# AS3364_DG412_bus_mixer_v1_3.net
KiCad netlist of a schematic drawn in EAGLE
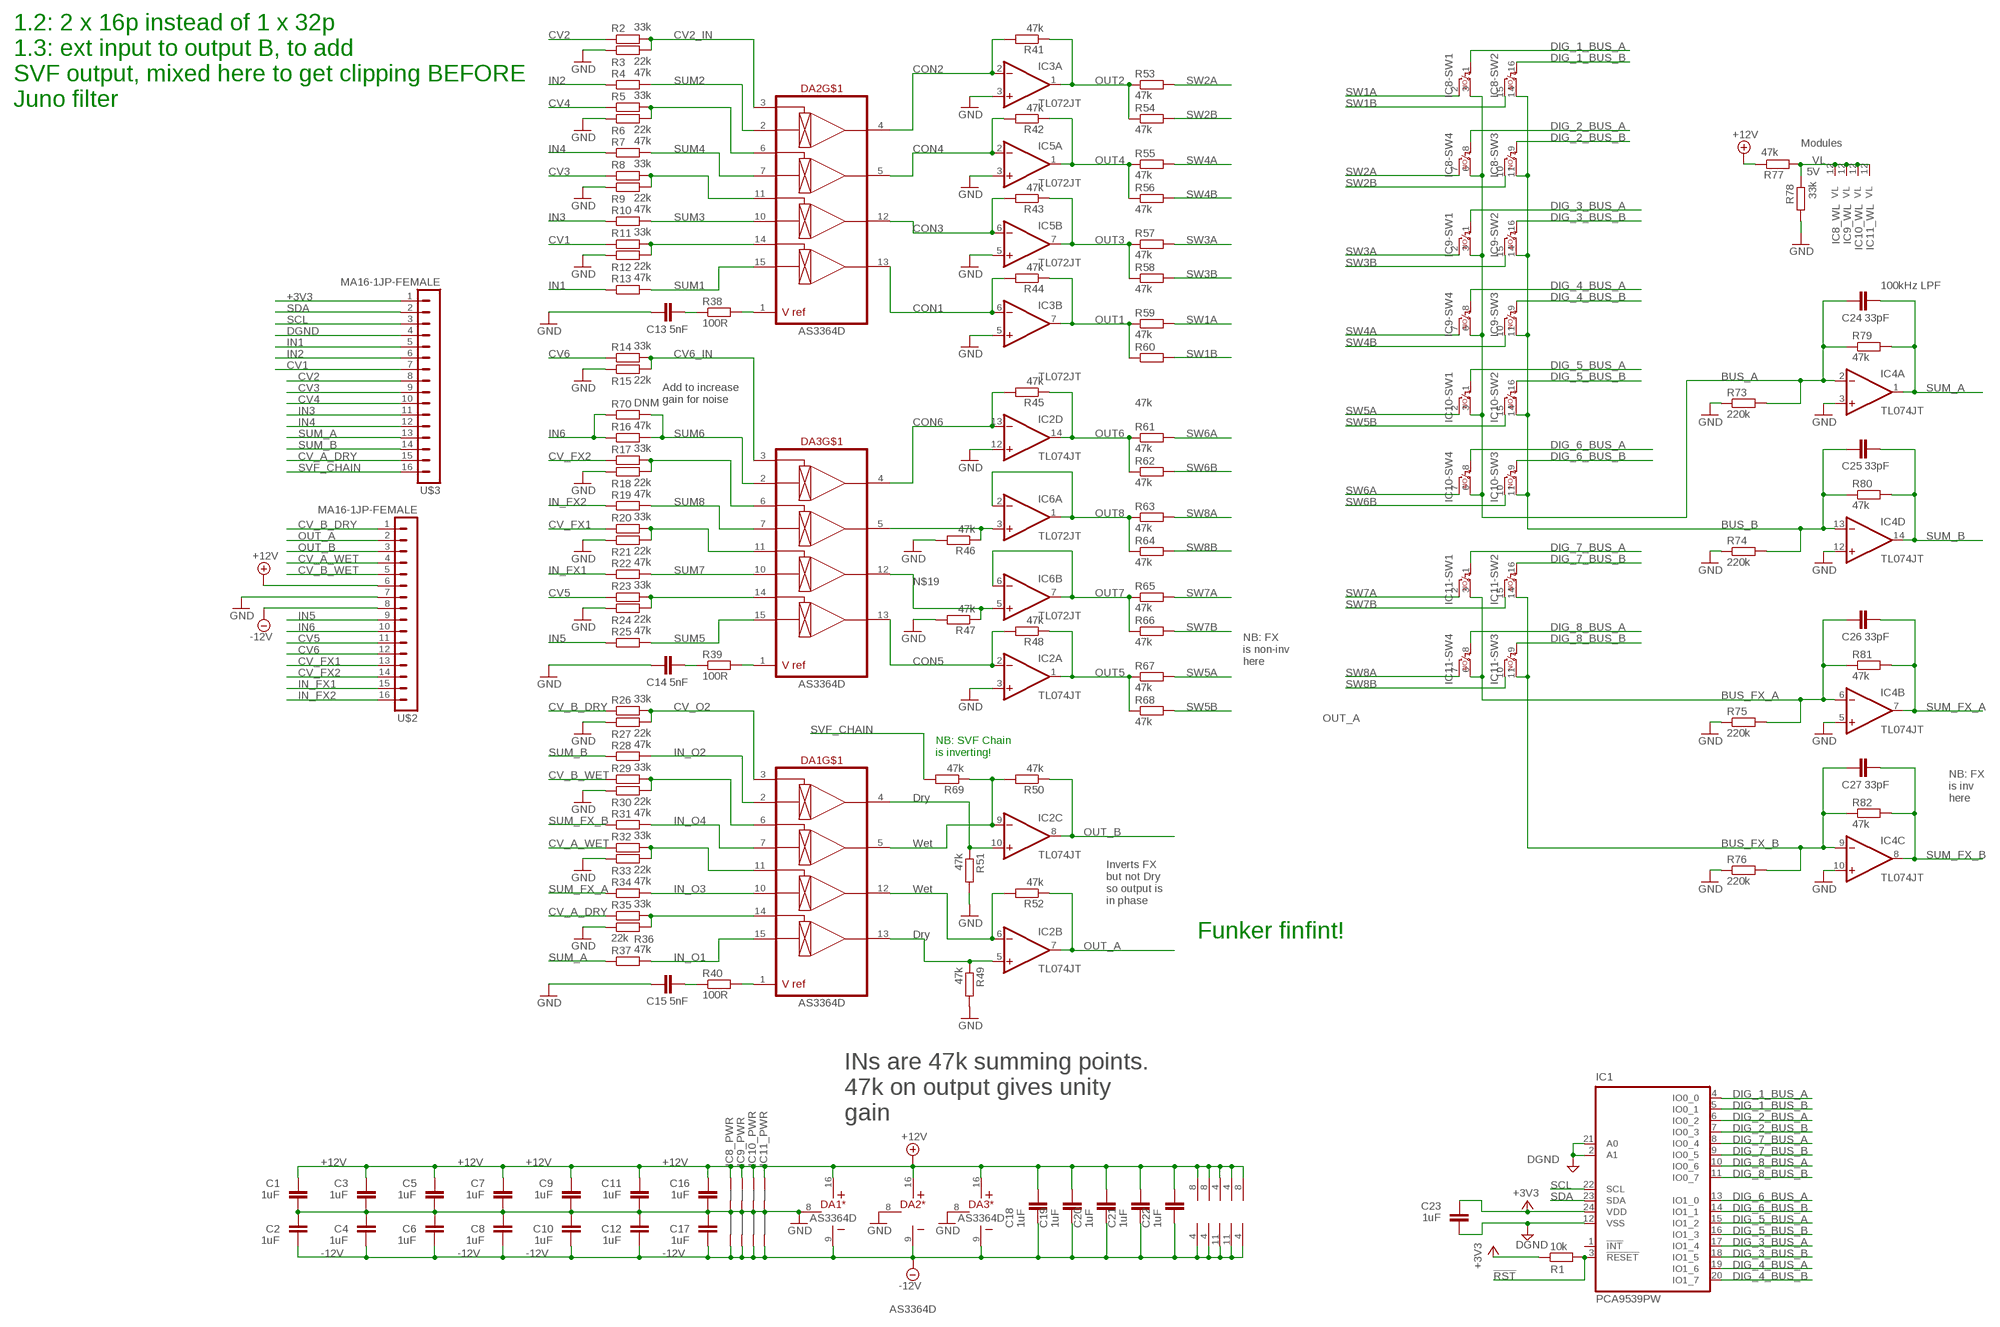
[diagram p0: schematic, sheet 1]

(export (version "E")
  (design (tool "Eeschema 10.0.6"))
  (components
    (comp (ref "C1")
      (value "1uF")
      (footprint "eagle-import:C0402-J")
      (libsource (lib "eagle-import") (part "C-EU-J0402"))
    )
    (comp (ref "C2")
      (value "1uF")
      (footprint "eagle-import:C0402-J")
      (libsource (lib "eagle-import") (part "C-EU-J0402"))
    )
    (comp (ref "C3")
      (value "1uF")
      (footprint "eagle-import:C0402-J")
      (libsource (lib "eagle-import") (part "C-EU-J0402"))
    )
    (comp (ref "C4")
      (value "1uF")
      (footprint "eagle-import:C0402-J")
      (libsource (lib "eagle-import") (part "C-EU-J0402"))
    )
    (comp (ref "C5")
      (value "1uF")
      (footprint "eagle-import:C0402-J")
      (libsource (lib "eagle-import") (part "C-EU-J0402"))
    )
    (comp (ref "C6")
      (value "1uF")
      (footprint "eagle-import:C0402-J")
      (libsource (lib "eagle-import") (part "C-EU-J0402"))
    )
    (comp (ref "C7")
      (value "1uF")
      (footprint "eagle-import:C0402-J")
      (libsource (lib "eagle-import") (part "C-EU-J0402"))
    )
    (comp (ref "C8")
      (value "1uF")
      (footprint "eagle-import:C0402-J")
      (libsource (lib "eagle-import") (part "C-EU-J0402"))
    )
    (comp (ref "C9")
      (value "1uF")
      (footprint "eagle-import:C0402-J")
      (libsource (lib "eagle-import") (part "C-EU-J0402"))
    )
    (comp (ref "C10")
      (value "1uF")
      (footprint "eagle-import:C0402-J")
      (libsource (lib "eagle-import") (part "C-EU-J0402"))
    )
    (comp (ref "C11")
      (value "1uF")
      (footprint "eagle-import:C0402-J")
      (libsource (lib "eagle-import") (part "C-EU-J0402"))
    )
    (comp (ref "C12")
      (value "1uF")
      (footprint "eagle-import:C0402-J")
      (libsource (lib "eagle-import") (part "C-EU-J0402"))
    )
    (comp (ref "C13")
      (value "5nF")
      (footprint "eagle-import:C0402-J")
      (libsource (lib "eagle-import") (part "C-EU-J0402"))
    )
    (comp (ref "C14")
      (value "5nF")
      (footprint "eagle-import:C0402-J")
      (libsource (lib "eagle-import") (part "C-EU-J0402"))
    )
    (comp (ref "C15")
      (value "5nF")
      (footprint "eagle-import:C0402-J")
      (libsource (lib "eagle-import") (part "C-EU-J0402"))
    )
    (comp (ref "C16")
      (value "1uF")
      (footprint "eagle-import:C0402-J")
      (libsource (lib "eagle-import") (part "C-EU-J0402"))
    )
    (comp (ref "C17")
      (value "1uF")
      (footprint "eagle-import:C0402-J")
      (libsource (lib "eagle-import") (part "C-EU-J0402"))
    )
    (comp (ref "C18")
      (value "1uF")
      (footprint "eagle-import:C0402")
      (libsource (lib "eagle-import") (part "C-EUC0402"))
    )
    (comp (ref "C19")
      (value "1uF")
      (footprint "eagle-import:C0402")
      (libsource (lib "eagle-import") (part "C-EUC0402"))
    )
    (comp (ref "C20")
      (value "1uF")
      (footprint "eagle-import:C0402")
      (libsource (lib "eagle-import") (part "C-EUC0402"))
    )
    (comp (ref "C21")
      (value "1uF")
      (footprint "eagle-import:C0402")
      (libsource (lib "eagle-import") (part "C-EUC0402"))
    )
    (comp (ref "C22")
      (value "1uF")
      (footprint "eagle-import:C0402")
      (libsource (lib "eagle-import") (part "C-EUC0402"))
    )
    (comp (ref "C23")
      (value "1uF")
      (footprint "eagle-import:C0402")
      (libsource (lib "eagle-import") (part "C-EUC0402"))
    )
    (comp (ref "C24")
      (value "33pF")
      (footprint "eagle-import:C0402-J")
      (libsource (lib "eagle-import") (part "C-EU-J0402"))
    )
    (comp (ref "C25")
      (value "33pF")
      (footprint "eagle-import:C0402-J")
      (libsource (lib "eagle-import") (part "C-EU-J0402"))
    )
    (comp (ref "C26")
      (value "33pF")
      (footprint "eagle-import:C0402-J")
      (libsource (lib "eagle-import") (part "C-EU-J0402"))
    )
    (comp (ref "C27")
      (value "33pF")
      (footprint "eagle-import:C0402-J")
      (libsource (lib "eagle-import") (part "C-EU-J0402"))
    )
    (comp (ref "DA1")
      (value "AS3364D")
      (footprint "eagle-import:DIL16J")
      (libsource (lib "eagle-import") (part "AS3364D"))
    )
    (comp (ref "DA2")
      (value "AS3364D")
      (footprint "eagle-import:DIL16J")
      (libsource (lib "eagle-import") (part "AS3364D"))
    )
    (comp (ref "DA3")
      (value "AS3364D")
      (footprint "eagle-import:DIL16J")
      (libsource (lib "eagle-import") (part "AS3364D"))
    )
    (comp (ref "IC1")
      (value "PCA9539PW")
      (footprint "eagle-import:TSSOP24J")
      (libsource (lib "eagle-import") (part "PCA9539PW"))
    )
    (comp (ref "IC2")
      (value "TL074JT")
      (footprint "eagle-import:TSSOP14J")
      (libsource (lib "eagle-import") (part "TL074JT"))
    )
    (comp (ref "IC3")
      (value "TL072JT")
      (footprint "eagle-import:TSSOP8J")
      (libsource (lib "eagle-import") (part "TL072JT"))
    )
    (comp (ref "IC4")
      (value "TL074JT")
      (footprint "eagle-import:TSSOP14J")
      (libsource (lib "eagle-import") (part "TL074JT"))
    )
    (comp (ref "IC5")
      (value "TL072JT")
      (footprint "eagle-import:TSSOP8J")
      (libsource (lib "eagle-import") (part "TL072JT"))
    )
    (comp (ref "IC6")
      (value "TL072JT")
      (footprint "eagle-import:TSSOP8J")
      (libsource (lib "eagle-import") (part "TL072JT"))
    )
    (comp (ref "IC8")
      (value "DG412-J")
      (footprint "eagle-import:DIL16J")
      (libsource (lib "eagle-import") (part "DG412-J"))
    )
    (comp (ref "IC9")
      (value "DG412-J")
      (footprint "eagle-import:DIL16J")
      (libsource (lib "eagle-import") (part "DG412-J"))
    )
    (comp (ref "IC10")
      (value "DG412-J")
      (footprint "eagle-import:DIL16J")
      (libsource (lib "eagle-import") (part "DG412-J"))
    )
    (comp (ref "IC11")
      (value "DG412-J")
      (footprint "eagle-import:DIL16J")
      (libsource (lib "eagle-import") (part "DG412-J"))
    )
    (comp (ref "R1")
      (value "10k")
      (footprint "eagle-import:R0402")
      (libsource (lib "eagle-import") (part "R-EU_R0402"))
    )
    (comp (ref "R2")
      (value "33k")
      (footprint "eagle-import:R0402")
      (libsource (lib "eagle-import") (part "R-EU_R0402"))
    )
    (comp (ref "R3")
      (value "22k")
      (footprint "eagle-import:R0402")
      (libsource (lib "eagle-import") (part "R-EU_R0402"))
    )
    (comp (ref "R4")
      (value "47k")
      (footprint "eagle-import:R0402")
      (libsource (lib "eagle-import") (part "R-EU_R0402"))
    )
    (comp (ref "R5")
      (value "33k")
      (footprint "eagle-import:R0402")
      (libsource (lib "eagle-import") (part "R-EU_R0402"))
    )
    (comp (ref "R6")
      (value "22k")
      (footprint "eagle-import:R0402")
      (libsource (lib "eagle-import") (part "R-EU_R0402"))
    )
    (comp (ref "R7")
      (value "47k")
      (footprint "eagle-import:R0402")
      (libsource (lib "eagle-import") (part "R-EU_R0402"))
    )
    (comp (ref "R8")
      (value "33k")
      (footprint "eagle-import:R0402")
      (libsource (lib "eagle-import") (part "R-EU_R0402"))
    )
    (comp (ref "R9")
      (value "22k")
      (footprint "eagle-import:R0402")
      (libsource (lib "eagle-import") (part "R-EU_R0402"))
    )
    (comp (ref "R10")
      (value "47k")
      (footprint "eagle-import:R0402")
      (libsource (lib "eagle-import") (part "R-EU_R0402"))
    )
    (comp (ref "R11")
      (value "33k")
      (footprint "eagle-import:R0402")
      (libsource (lib "eagle-import") (part "R-EU_R0402"))
    )
    (comp (ref "R12")
      (value "22k")
      (footprint "eagle-import:R0402")
      (libsource (lib "eagle-import") (part "R-EU_R0402"))
    )
    (comp (ref "R13")
      (value "47k")
      (footprint "eagle-import:R0402")
      (libsource (lib "eagle-import") (part "R-EU_R0402"))
    )
    (comp (ref "R14")
      (value "33k")
      (footprint "eagle-import:R0402")
      (libsource (lib "eagle-import") (part "R-EU_R0402"))
    )
    (comp (ref "R15")
      (value "22k")
      (footprint "eagle-import:R0402")
      (libsource (lib "eagle-import") (part "R-EU_R0402"))
    )
    (comp (ref "R16")
      (value "47k")
      (footprint "eagle-import:R0402")
      (libsource (lib "eagle-import") (part "R-EU_R0402"))
    )
    (comp (ref "R17")
      (value "33k")
      (footprint "eagle-import:R0402")
      (libsource (lib "eagle-import") (part "R-EU_R0402"))
    )
    (comp (ref "R18")
      (value "22k")
      (footprint "eagle-import:R0402")
      (libsource (lib "eagle-import") (part "R-EU_R0402"))
    )
    (comp (ref "R19")
      (value "47k")
      (footprint "eagle-import:R0402")
      (libsource (lib "eagle-import") (part "R-EU_R0402"))
    )
    (comp (ref "R20")
      (value "33k")
      (footprint "eagle-import:R0402")
      (libsource (lib "eagle-import") (part "R-EU_R0402"))
    )
    (comp (ref "R21")
      (value "22k")
      (footprint "eagle-import:R0402")
      (libsource (lib "eagle-import") (part "R-EU_R0402"))
    )
    (comp (ref "R22")
      (value "47k")
      (footprint "eagle-import:R0402")
      (libsource (lib "eagle-import") (part "R-EU_R0402"))
    )
    (comp (ref "R23")
      (value "33k")
      (footprint "eagle-import:R0402")
      (libsource (lib "eagle-import") (part "R-EU_R0402"))
    )
    (comp (ref "R24")
      (value "22k")
      (footprint "eagle-import:R0402")
      (libsource (lib "eagle-import") (part "R-EU_R0402"))
    )
    (comp (ref "R25")
      (value "47k")
      (footprint "eagle-import:R0402")
      (libsource (lib "eagle-import") (part "R-EU_R0402"))
    )
    (comp (ref "R26")
      (value "33k")
      (footprint "eagle-import:R0402")
      (libsource (lib "eagle-import") (part "R-EU_R0402"))
    )
    (comp (ref "R27")
      (value "22k")
      (footprint "eagle-import:R0402")
      (libsource (lib "eagle-import") (part "R-EU_R0402"))
    )
    (comp (ref "R28")
      (value "47k")
      (footprint "eagle-import:R0402")
      (libsource (lib "eagle-import") (part "R-EU_R0402"))
    )
    (comp (ref "R29")
      (value "33k")
      (footprint "eagle-import:R0402")
      (libsource (lib "eagle-import") (part "R-EU_R0402"))
    )
    (comp (ref "R30")
      (value "22k")
      (footprint "eagle-import:R0402")
      (libsource (lib "eagle-import") (part "R-EU_R0402"))
    )
    (comp (ref "R31")
      (value "47k")
      (footprint "eagle-import:R0402")
      (libsource (lib "eagle-import") (part "R-EU_R0402"))
    )
    (comp (ref "R32")
      (value "33k")
      (footprint "eagle-import:R0402")
      (libsource (lib "eagle-import") (part "R-EU_R0402"))
    )
    (comp (ref "R33")
      (value "22k")
      (footprint "eagle-import:R0402")
      (libsource (lib "eagle-import") (part "R-EU_R0402"))
    )
    (comp (ref "R34")
      (value "47k")
      (footprint "eagle-import:R0402")
      (libsource (lib "eagle-import") (part "R-EU_R0402"))
    )
    (comp (ref "R35")
      (value "33k")
      (footprint "eagle-import:R0402")
      (libsource (lib "eagle-import") (part "R-EU_R0402"))
    )
    (comp (ref "R36")
      (value "22k")
      (footprint "eagle-import:R0402")
      (libsource (lib "eagle-import") (part "R-EU_R0402"))
    )
    (comp (ref "R37")
      (value "47k")
      (footprint "eagle-import:R0402")
      (libsource (lib "eagle-import") (part "R-EU_R0402"))
    )
    (comp (ref "R38")
      (value "100R")
      (footprint "eagle-import:R0402")
      (libsource (lib "eagle-import") (part "R-EU_R0402"))
    )
    (comp (ref "R39")
      (value "100R")
      (footprint "eagle-import:R0402")
      (libsource (lib "eagle-import") (part "R-EU_R0402"))
    )
    (comp (ref "R40")
      (value "100R")
      (footprint "eagle-import:R0402")
      (libsource (lib "eagle-import") (part "R-EU_R0402"))
    )
    (comp (ref "R41")
      (value "47k")
      (footprint "eagle-import:R0402")
      (libsource (lib "eagle-import") (part "R-EU_R0402"))
    )
    (comp (ref "R42")
      (value "47k")
      (footprint "eagle-import:R0402")
      (libsource (lib "eagle-import") (part "R-EU_R0402"))
    )
    (comp (ref "R43")
      (value "47k")
      (footprint "eagle-import:R0402")
      (libsource (lib "eagle-import") (part "R-EU_R0402"))
    )
    (comp (ref "R44")
      (value "47k")
      (footprint "eagle-import:R0402")
      (libsource (lib "eagle-import") (part "R-EU_R0402"))
    )
    (comp (ref "R45")
      (value "47k")
      (footprint "eagle-import:R0402")
      (libsource (lib "eagle-import") (part "R-EU_R0402"))
    )
    (comp (ref "R46")
      (value "47k")
      (footprint "eagle-import:R0402")
      (libsource (lib "eagle-import") (part "R-EU_R0402"))
    )
    (comp (ref "R47")
      (value "47k")
      (footprint "eagle-import:R0402")
      (libsource (lib "eagle-import") (part "R-EU_R0402"))
    )
    (comp (ref "R48")
      (value "47k")
      (footprint "eagle-import:R0402")
      (libsource (lib "eagle-import") (part "R-EU_R0402"))
    )
    (comp (ref "R49")
      (value "47k")
      (footprint "eagle-import:R0402")
      (libsource (lib "eagle-import") (part "R-EU_R0402"))
    )
    (comp (ref "R50")
      (value "47k")
      (footprint "eagle-import:R0402")
      (libsource (lib "eagle-import") (part "R-EU_R0402"))
    )
    (comp (ref "R51")
      (value "47k")
      (footprint "eagle-import:R0402")
      (libsource (lib "eagle-import") (part "R-EU_R0402"))
    )
    (comp (ref "R52")
      (value "47k")
      (footprint "eagle-import:R0402")
      (libsource (lib "eagle-import") (part "R-EU_R0402"))
    )
    (comp (ref "R53")
      (value "47k")
      (footprint "eagle-import:R0402")
      (libsource (lib "eagle-import") (part "R-EU_R0402"))
    )
    (comp (ref "R54")
      (value "47k")
      (footprint "eagle-import:R0402")
      (libsource (lib "eagle-import") (part "R-EU_R0402"))
    )
    (comp (ref "R55")
      (value "47k")
      (footprint "eagle-import:R0402")
      (libsource (lib "eagle-import") (part "R-EU_R0402"))
    )
    (comp (ref "R56")
      (value "47k")
      (footprint "eagle-import:R0402")
      (libsource (lib "eagle-import") (part "R-EU_R0402"))
    )
    (comp (ref "R57")
      (value "47k")
      (footprint "eagle-import:R0402")
      (libsource (lib "eagle-import") (part "R-EU_R0402"))
    )
    (comp (ref "R58")
      (value "47k")
      (footprint "eagle-import:R0402")
      (libsource (lib "eagle-import") (part "R-EU_R0402"))
    )
    (comp (ref "R59")
      (value "47k")
      (footprint "eagle-import:R0402")
      (libsource (lib "eagle-import") (part "R-EU_R0402"))
    )
    (comp (ref "R60")
      (value "47k")
      (footprint "eagle-import:R0402")
      (libsource (lib "eagle-import") (part "R-EU_R0402"))
    )
    (comp (ref "R61")
      (value "47k")
      (footprint "eagle-import:R0402")
      (libsource (lib "eagle-import") (part "R-EU_R0402"))
    )
    (comp (ref "R62")
      (value "47k")
      (footprint "eagle-import:R0402")
      (libsource (lib "eagle-import") (part "R-EU_R0402"))
    )
    (comp (ref "R63")
      (value "47k")
      (footprint "eagle-import:R0402")
      (libsource (lib "eagle-import") (part "R-EU_R0402"))
    )
    (comp (ref "R64")
      (value "47k")
      (footprint "eagle-import:R0402")
      (libsource (lib "eagle-import") (part "R-EU_R0402"))
    )
    (comp (ref "R65")
      (value "47k")
      (footprint "eagle-import:R0402")
      (libsource (lib "eagle-import") (part "R-EU_R0402"))
    )
    (comp (ref "R66")
      (value "47k")
      (footprint "eagle-import:R0402")
      (libsource (lib "eagle-import") (part "R-EU_R0402"))
    )
    (comp (ref "R67")
      (value "47k")
      (footprint "eagle-import:R0402")
      (libsource (lib "eagle-import") (part "R-EU_R0402"))
    )
    (comp (ref "R68")
      (value "47k")
      (footprint "eagle-import:R0402")
      (libsource (lib "eagle-import") (part "R-EU_R0402"))
    )
    (comp (ref "R69")
      (value "47k")
      (footprint "eagle-import:R0402")
      (libsource (lib "eagle-import") (part "R-EU_R0402"))
    )
    (comp (ref "R70")
      (value "DNM")
      (footprint "eagle-import:R0805")
      (libsource (lib "eagle-import") (part "R-EU_R0805"))
    )
    (comp (ref "R73")
      (value "220k")
      (footprint "eagle-import:R0603")
      (libsource (lib "eagle-import") (part "R-EU_R0603"))
    )
    (comp (ref "R74")
      (value "220k")
      (footprint "eagle-import:R0603")
      (libsource (lib "eagle-import") (part "R-EU_R0603"))
    )
    (comp (ref "R75")
      (value "220k")
      (footprint "eagle-import:R0603")
      (libsource (lib "eagle-import") (part "R-EU_R0603"))
    )
    (comp (ref "R76")
      (value "220k")
      (footprint "eagle-import:R0603")
      (libsource (lib "eagle-import") (part "R-EU_R0603"))
    )
    (comp (ref "R77")
      (value "47k")
      (footprint "eagle-import:R0402")
      (libsource (lib "eagle-import") (part "R-EU_R0402"))
    )
    (comp (ref "R78")
      (value "33k")
      (footprint "eagle-import:R0402")
      (libsource (lib "eagle-import") (part "R-EU_R0402"))
    )
    (comp (ref "R79")
      (value "47k")
      (footprint "eagle-import:R0402")
      (libsource (lib "eagle-import") (part "R-EU_R0402"))
    )
    (comp (ref "R80")
      (value "47k")
      (footprint "eagle-import:R0402")
      (libsource (lib "eagle-import") (part "R-EU_R0402"))
    )
    (comp (ref "R81")
      (value "47k")
      (footprint "eagle-import:R0402")
      (libsource (lib "eagle-import") (part "R-EU_R0402"))
    )
    (comp (ref "R82")
      (value "47k")
      (footprint "eagle-import:R0402")
      (libsource (lib "eagle-import") (part "R-EU_R0402"))
    )
    (comp (ref "U$2")
      (value "MA16-1JP-FEMALE")
      (footprint "eagle-import:SIP-PIN16-1J")
      (libsource (lib "eagle-import") (part "MA16-1JP"))
    )
    (comp (ref "U$3")
      (value "MA16-1JP-FEMALE")
      (footprint "eagle-import:SIP-PIN16-1J")
      (libsource (lib "eagle-import") (part "MA16-1JP"))
    )
  )
  (nets
    (net (code "1") (name "+3V3") (class "Default")
      (node (ref "C23") (pin "2") (pinfunction "2_2") (pintype "passive"))
      (node (ref "IC1") (pin "24") (pinfunction "VDD_24") (pintype "power_in"))
      (node (ref "R1") (pin "1") (pinfunction "1_1") (pintype "passive"))
      (node (ref "U$3") (pin "1") (pinfunction "1_1") (pintype "passive"))
    )
    (net (code "2") (name "+12V") (class "Default")
      (node (ref "C1") (pin "2") (pinfunction "2_2") (pintype "passive"))
      (node (ref "C11") (pin "2") (pinfunction "2_2") (pintype "passive"))
      (node (ref "C16") (pin "2") (pinfunction "2_2") (pintype "passive"))
      (node (ref "C18") (pin "2") (pinfunction "2_2") (pintype "passive"))
      (node (ref "C19") (pin "2") (pinfunction "2_2") (pintype "passive"))
      (node (ref "C20") (pin "2") (pinfunction "2_2") (pintype "passive"))
      (node (ref "C21") (pin "2") (pinfunction "2_2") (pintype "passive"))
      (node (ref "C22") (pin "2") (pinfunction "2_2") (pintype "passive"))
      (node (ref "C3") (pin "2") (pinfunction "2_2") (pintype "passive"))
      (node (ref "C5") (pin "2") (pinfunction "2_2") (pintype "passive"))
      (node (ref "C7") (pin "2") (pinfunction "2_2") (pintype "passive"))
      (node (ref "C9") (pin "2") (pinfunction "2_2") (pintype "passive"))
      (node (ref "DA1") (pin "16") (pinfunction "V+_16") (pintype "power_in"))
      (node (ref "DA2") (pin "16") (pinfunction "V+_16") (pintype "power_in"))
      (node (ref "DA3") (pin "16") (pinfunction "V+_16") (pintype "power_in"))
      (node (ref "IC10") (pin "13") (pinfunction "+15V_13") (pintype "power_in"))
      (node (ref "IC11") (pin "13") (pinfunction "+15V_13") (pintype "power_in"))
      (node (ref "IC2") (pin "4") (pinfunction "V+_4") (pintype "power_in"))
      (node (ref "IC3") (pin "8") (pinfunction "V+_8") (pintype "power_in"))
      (node (ref "IC4") (pin "4") (pinfunction "V+_4") (pintype "power_in"))
      (node (ref "IC5") (pin "8") (pinfunction "V+_8") (pintype "power_in"))
      (node (ref "IC6") (pin "8") (pinfunction "V+_8") (pintype "power_in"))
      (node (ref "IC8") (pin "13") (pinfunction "+15V_13") (pintype "power_in"))
      (node (ref "IC9") (pin "13") (pinfunction "+15V_13") (pintype "power_in"))
      (node (ref "R77") (pin "1") (pinfunction "1_1") (pintype "passive"))
      (node (ref "U$2") (pin "6") (pinfunction "6_6") (pintype "passive"))
    )
    (net (code "3") (name "-12V") (class "Default")
      (node (ref "C10") (pin "1") (pinfunction "1_1") (pintype "passive"))
      (node (ref "C12") (pin "1") (pinfunction "1_1") (pintype "passive"))
      (node (ref "C17") (pin "1") (pinfunction "1_1") (pintype "passive"))
      (node (ref "C18") (pin "1") (pinfunction "1_1") (pintype "passive"))
      (node (ref "C19") (pin "1") (pinfunction "1_1") (pintype "passive"))
      (node (ref "C2") (pin "1") (pinfunction "1_1") (pintype "passive"))
      (node (ref "C20") (pin "1") (pinfunction "1_1") (pintype "passive"))
      (node (ref "C21") (pin "1") (pinfunction "1_1") (pintype "passive"))
      (node (ref "C22") (pin "1") (pinfunction "1_1") (pintype "passive"))
      (node (ref "C4") (pin "1") (pinfunction "1_1") (pintype "passive"))
      (node (ref "C6") (pin "1") (pinfunction "1_1") (pintype "passive"))
      (node (ref "C8") (pin "1") (pinfunction "1_1") (pintype "passive"))
      (node (ref "DA1") (pin "9") (pinfunction "V-_9") (pintype "power_in"))
      (node (ref "DA2") (pin "9") (pinfunction "V-_9") (pintype "power_in"))
      (node (ref "DA3") (pin "9") (pinfunction "V-_9") (pintype "power_in"))
      (node (ref "IC10") (pin "4") (pinfunction "-15V_4") (pintype "power_in"))
      (node (ref "IC11") (pin "4") (pinfunction "-15V_4") (pintype "power_in"))
      (node (ref "IC2") (pin "11") (pinfunction "V-_11") (pintype "power_in"))
      (node (ref "IC3") (pin "4") (pinfunction "V-_4") (pintype "power_in"))
      (node (ref "IC4") (pin "11") (pinfunction "V-_11") (pintype "power_in"))
      (node (ref "IC5") (pin "4") (pinfunction "V-_4") (pintype "power_in"))
      (node (ref "IC6") (pin "4") (pinfunction "V-_4") (pintype "power_in"))
      (node (ref "IC8") (pin "4") (pinfunction "-15V_4") (pintype "power_in"))
      (node (ref "IC9") (pin "4") (pinfunction "-15V_4") (pintype "power_in"))
      (node (ref "U$2") (pin "8") (pinfunction "8_8") (pintype "passive"))
    )
    (net (code "4") (name "/BUS_A") (class "Default")
      (node (ref "C24") (pin "1") (pinfunction "1_1") (pintype "passive"))
      (node (ref "IC10") (pin "3") (pinfunction "S_3") (pintype "bidirectional"))
      (node (ref "IC10") (pin "6") (pinfunction "S_6") (pintype "bidirectional"))
      (node (ref "IC4") (pin "2") (pinfunction "-IN_2") (pintype "input"))
      (node (ref "IC8") (pin "3") (pinfunction "S_3") (pintype "bidirectional"))
      (node (ref "IC8") (pin "6") (pinfunction "S_6") (pintype "bidirectional"))
      (node (ref "IC9") (pin "3") (pinfunction "S_3") (pintype "bidirectional"))
      (node (ref "IC9") (pin "6") (pinfunction "S_6") (pintype "bidirectional"))
      (node (ref "R73") (pin "2") (pinfunction "2_2") (pintype "passive"))
      (node (ref "R79") (pin "1") (pinfunction "1_1") (pintype "passive"))
    )
    (net (code "5") (name "/BUS_B") (class "Default")
      (node (ref "C25") (pin "1") (pinfunction "1_1") (pintype "passive"))
      (node (ref "IC10") (pin "11") (pinfunction "S_11") (pintype "bidirectional"))
      (node (ref "IC10") (pin "14") (pinfunction "S_14") (pintype "bidirectional"))
      (node (ref "IC4") (pin "13") (pinfunction "-IN_13") (pintype "input"))
      (node (ref "IC8") (pin "11") (pinfunction "S_11") (pintype "bidirectional"))
      (node (ref "IC8") (pin "14") (pinfunction "S_14") (pintype "bidirectional"))
      (node (ref "IC9") (pin "11") (pinfunction "S_11") (pintype "bidirectional"))
      (node (ref "IC9") (pin "14") (pinfunction "S_14") (pintype "bidirectional"))
      (node (ref "R74") (pin "2") (pinfunction "2_2") (pintype "passive"))
      (node (ref "R80") (pin "1") (pinfunction "1_1") (pintype "passive"))
    )
    (net (code "6") (name "/BUS_FX_A") (class "Default")
      (node (ref "C26") (pin "1") (pinfunction "1_1") (pintype "passive"))
      (node (ref "IC11") (pin "3") (pinfunction "S_3") (pintype "bidirectional"))
      (node (ref "IC11") (pin "6") (pinfunction "S_6") (pintype "bidirectional"))
      (node (ref "IC4") (pin "6") (pinfunction "-IN_6") (pintype "input"))
      (node (ref "R75") (pin "2") (pinfunction "2_2") (pintype "passive"))
      (node (ref "R81") (pin "1") (pinfunction "1_1") (pintype "passive"))
    )
    (net (code "7") (name "/BUS_FX_B") (class "Default")
      (node (ref "C27") (pin "1") (pinfunction "1_1") (pintype "passive"))
      (node (ref "IC11") (pin "11") (pinfunction "S_11") (pintype "bidirectional"))
      (node (ref "IC11") (pin "14") (pinfunction "S_14") (pintype "bidirectional"))
      (node (ref "IC4") (pin "9") (pinfunction "-IN_9") (pintype "input"))
      (node (ref "R76") (pin "2") (pinfunction "2_2") (pintype "passive"))
      (node (ref "R82") (pin "1") (pinfunction "1_1") (pintype "passive"))
    )
    (net (code "8") (name "/CON1") (class "Default")
      (node (ref "DA2") (pin "13") (pinfunction "OUT4_13") (pintype "output"))
      (node (ref "IC3") (pin "6") (pinfunction "-IN_6") (pintype "input"))
      (node (ref "R44") (pin "2") (pinfunction "2_2") (pintype "passive"))
    )
    (net (code "9") (name "/CON2") (class "Default")
      (node (ref "DA2") (pin "4") (pinfunction "OUT1_4") (pintype "output"))
      (node (ref "IC3") (pin "2") (pinfunction "-IN_2") (pintype "input"))
      (node (ref "R41") (pin "2") (pinfunction "2_2") (pintype "passive"))
    )
    (net (code "10") (name "/CON3") (class "Default")
      (node (ref "DA2") (pin "12") (pinfunction "OUT3_12") (pintype "output"))
      (node (ref "IC5") (pin "6") (pinfunction "-IN_6") (pintype "input"))
      (node (ref "R43") (pin "2") (pinfunction "2_2") (pintype "passive"))
    )
    (net (code "11") (name "/CON4") (class "Default")
      (node (ref "DA2") (pin "5") (pinfunction "OUT2_5") (pintype "output"))
      (node (ref "IC5") (pin "2") (pinfunction "-IN_2") (pintype "input"))
      (node (ref "R42") (pin "2") (pinfunction "2_2") (pintype "passive"))
    )
    (net (code "12") (name "/CON5") (class "Default")
      (node (ref "DA3") (pin "13") (pinfunction "OUT4_13") (pintype "output"))
      (node (ref "IC2") (pin "2") (pinfunction "-IN_2") (pintype "input"))
      (node (ref "R48") (pin "2") (pinfunction "2_2") (pintype "passive"))
    )
    (net (code "13") (name "/CON6") (class "Default")
      (node (ref "DA3") (pin "4") (pinfunction "OUT1_4") (pintype "output"))
      (node (ref "IC2") (pin "13") (pinfunction "-IN_13") (pintype "input"))
      (node (ref "R45") (pin "2") (pinfunction "2_2") (pintype "passive"))
    )
    (net (code "14") (name "/CV1") (class "Default")
      (node (ref "R11") (pin "1") (pinfunction "1_1") (pintype "passive"))
      (node (ref "U$3") (pin "7") (pinfunction "7_7") (pintype "passive"))
    )
    (net (code "15") (name "/CV2") (class "Default")
      (node (ref "R2") (pin "1") (pinfunction "1_1") (pintype "passive"))
      (node (ref "U$3") (pin "8") (pinfunction "8_8") (pintype "passive"))
    )
    (net (code "16") (name "/CV2_IN") (class "Default")
      (node (ref "DA2") (pin "3") (pinfunction "CV1_3") (pintype "input"))
      (node (ref "R2") (pin "2") (pinfunction "2_2") (pintype "passive"))
      (node (ref "R3") (pin "2") (pinfunction "2_2") (pintype "passive"))
    )
    (net (code "17") (name "/CV3") (class "Default")
      (node (ref "R8") (pin "1") (pinfunction "1_1") (pintype "passive"))
      (node (ref "U$3") (pin "9") (pinfunction "9_9") (pintype "passive"))
    )
    (net (code "18") (name "/CV4") (class "Default")
      (node (ref "R5") (pin "1") (pinfunction "1_1") (pintype "passive"))
      (node (ref "U$3") (pin "10") (pinfunction "10_10") (pintype "passive"))
    )
    (net (code "19") (name "/CV5") (class "Default")
      (node (ref "R23") (pin "1") (pinfunction "1_1") (pintype "passive"))
      (node (ref "U$2") (pin "11") (pinfunction "11_11") (pintype "passive"))
    )
    (net (code "20") (name "/CV6") (class "Default")
      (node (ref "R14") (pin "1") (pinfunction "1_1") (pintype "passive"))
      (node (ref "U$2") (pin "12") (pinfunction "12_12") (pintype "passive"))
    )
    (net (code "21") (name "/CV6_IN") (class "Default")
      (node (ref "DA3") (pin "3") (pinfunction "CV1_3") (pintype "input"))
      (node (ref "R14") (pin "2") (pinfunction "2_2") (pintype "passive"))
      (node (ref "R15") (pin "2") (pinfunction "2_2") (pintype "passive"))
    )
    (net (code "22") (name "/CV_A_DRY") (class "Default")
      (node (ref "R35") (pin "1") (pinfunction "1_1") (pintype "passive"))
      (node (ref "U$3") (pin "15") (pinfunction "15_15") (pintype "passive"))
    )
    (net (code "23") (name "/CV_A_WET") (class "Default")
      (node (ref "R32") (pin "1") (pinfunction "1_1") (pintype "passive"))
      (node (ref "U$2") (pin "4") (pinfunction "4_4") (pintype "passive"))
    )
    (net (code "24") (name "/CV_B_DRY") (class "Default")
      (node (ref "R26") (pin "1") (pinfunction "1_1") (pintype "passive"))
      (node (ref "U$2") (pin "1") (pinfunction "1_1") (pintype "passive"))
    )
    (net (code "25") (name "/CV_B_WET") (class "Default")
      (node (ref "R29") (pin "1") (pinfunction "1_1") (pintype "passive"))
      (node (ref "U$2") (pin "5") (pinfunction "5_5") (pintype "passive"))
    )
    (net (code "26") (name "/CV_FX1") (class "Default")
      (node (ref "R20") (pin "1") (pinfunction "1_1") (pintype "passive"))
      (node (ref "U$2") (pin "13") (pinfunction "13_13") (pintype "passive"))
    )
    (net (code "27") (name "/CV_FX2") (class "Default")
      (node (ref "R17") (pin "1") (pinfunction "1_1") (pintype "passive"))
      (node (ref "U$2") (pin "14") (pinfunction "14_14") (pintype "passive"))
    )
    (net (code "28") (name "/CV_O2") (class "Default")
      (node (ref "DA1") (pin "3") (pinfunction "CV1_3") (pintype "input"))
      (node (ref "R26") (pin "2") (pinfunction "2_2") (pintype "passive"))
      (node (ref "R27") (pin "2") (pinfunction "2_2") (pintype "passive"))
    )
    (net (code "29") (name "/DIG_1_BUS_A") (class "Default")
      (node (ref "IC1") (pin "4") (pinfunction "IO0_0_4") (pintype "bidirectional"))
      (node (ref "IC8") (pin "1") (pinfunction "C_1") (pintype "bidirectional"))
    )
    (net (code "30") (name "/DIG_1_BUS_B") (class "Default")
      (node (ref "IC1") (pin "5") (pinfunction "IO0_1_5") (pintype "bidirectional"))
      (node (ref "IC8") (pin "16") (pinfunction "C_16") (pintype "bidirectional"))
    )
    (net (code "31") (name "/DIG_2_BUS_A") (class "Default")
      (node (ref "IC1") (pin "6") (pinfunction "IO0_2_6") (pintype "bidirectional"))
      (node (ref "IC8") (pin "8") (pinfunction "C_8") (pintype "bidirectional"))
    )
    (net (code "32") (name "/DIG_2_BUS_B") (class "Default")
      (node (ref "IC1") (pin "7") (pinfunction "IO0_3_7") (pintype "bidirectional"))
      (node (ref "IC8") (pin "9") (pinfunction "C_9") (pintype "bidirectional"))
    )
    (net (code "33") (name "/DIG_3_BUS_A") (class "Default")
      (node (ref "IC1") (pin "17") (pinfunction "IO1_4_17") (pintype "bidirectional"))
      (node (ref "IC9") (pin "1") (pinfunction "C_1") (pintype "bidirectional"))
    )
    (net (code "34") (name "/DIG_3_BUS_B") (class "Default")
      (node (ref "IC1") (pin "18") (pinfunction "IO1_5_18") (pintype "bidirectional"))
      (node (ref "IC9") (pin "16") (pinfunction "C_16") (pintype "bidirectional"))
    )
    (net (code "35") (name "/DIG_4_BUS_A") (class "Default")
      (node (ref "IC1") (pin "19") (pinfunction "IO1_6_19") (pintype "bidirectional"))
      (node (ref "IC9") (pin "8") (pinfunction "C_8") (pintype "bidirectional"))
    )
    (net (code "36") (name "/DIG_4_BUS_B") (class "Default")
      (node (ref "IC1") (pin "20") (pinfunction "IO1_7_20") (pintype "bidirectional"))
      (node (ref "IC9") (pin "9") (pinfunction "C_9") (pintype "bidirectional"))
    )
    (net (code "37") (name "/DIG_5_BUS_A") (class "Default")
      (node (ref "IC1") (pin "15") (pinfunction "IO1_2_15") (pintype "bidirectional"))
      (node (ref "IC10") (pin "1") (pinfunction "C_1") (pintype "bidirectional"))
    )
    (net (code "38") (name "/DIG_5_BUS_B") (class "Default")
      (node (ref "IC1") (pin "16") (pinfunction "IO1_3_16") (pintype "bidirectional"))
      (node (ref "IC10") (pin "16") (pinfunction "C_16") (pintype "bidirectional"))
    )
    (net (code "39") (name "/DIG_6_BUS_A") (class "Default")
      (node (ref "IC1") (pin "13") (pinfunction "IO1_0_13") (pintype "bidirectional"))
      (node (ref "IC10") (pin "8") (pinfunction "C_8") (pintype "bidirectional"))
    )
    (net (code "40") (name "/DIG_6_BUS_B") (class "Default")
      (node (ref "IC1") (pin "14") (pinfunction "IO1_1_14") (pintype "bidirectional"))
      (node (ref "IC10") (pin "9") (pinfunction "C_9") (pintype "bidirectional"))
    )
    (net (code "41") (name "/DIG_7_BUS_A") (class "Default")
      (node (ref "IC1") (pin "8") (pinfunction "IO0_4_8") (pintype "bidirectional"))
      (node (ref "IC11") (pin "1") (pinfunction "C_1") (pintype "bidirectional"))
    )
    (net (code "42") (name "/DIG_7_BUS_B") (class "Default")
      (node (ref "IC1") (pin "9") (pinfunction "IO0_5_9") (pintype "bidirectional"))
      (node (ref "IC11") (pin "16") (pinfunction "C_16") (pintype "bidirectional"))
    )
    (net (code "43") (name "/DIG_8_BUS_A") (class "Default")
      (node (ref "IC1") (pin "10") (pinfunction "IO0_6_10") (pintype "bidirectional"))
      (node (ref "IC11") (pin "8") (pinfunction "C_8") (pintype "bidirectional"))
    )
    (net (code "44") (name "/DIG_8_BUS_B") (class "Default")
      (node (ref "IC1") (pin "11") (pinfunction "IO0_7_11") (pintype "bidirectional"))
      (node (ref "IC11") (pin "9") (pinfunction "C_9") (pintype "bidirectional"))
    )
    (net (code "45") (name "/IN1") (class "Default")
      (node (ref "R13") (pin "1") (pinfunction "1_1") (pintype "passive"))
      (node (ref "U$3") (pin "5") (pinfunction "5_5") (pintype "passive"))
    )
    (net (code "46") (name "/IN2") (class "Default")
      (node (ref "R4") (pin "1") (pinfunction "1_1") (pintype "passive"))
      (node (ref "U$3") (pin "6") (pinfunction "6_6") (pintype "passive"))
    )
    (net (code "47") (name "/IN3") (class "Default")
      (node (ref "R10") (pin "1") (pinfunction "1_1") (pintype "passive"))
      (node (ref "U$3") (pin "11") (pinfunction "11_11") (pintype "passive"))
    )
    (net (code "48") (name "/IN4") (class "Default")
      (node (ref "R7") (pin "1") (pinfunction "1_1") (pintype "passive"))
      (node (ref "U$3") (pin "12") (pinfunction "12_12") (pintype "passive"))
    )
    (net (code "49") (name "/IN5") (class "Default")
      (node (ref "R25") (pin "1") (pinfunction "1_1") (pintype "passive"))
      (node (ref "U$2") (pin "9") (pinfunction "9_9") (pintype "passive"))
    )
    (net (code "50") (name "/IN6") (class "Default")
      (node (ref "R16") (pin "1") (pinfunction "1_1") (pintype "passive"))
      (node (ref "R70") (pin "1") (pinfunction "1_1") (pintype "passive"))
      (node (ref "U$2") (pin "10") (pinfunction "10_10") (pintype "passive"))
    )
    (net (code "51") (name "/IN_FX1") (class "Default")
      (node (ref "R22") (pin "1") (pinfunction "1_1") (pintype "passive"))
      (node (ref "U$2") (pin "15") (pinfunction "15_15") (pintype "passive"))
    )
    (net (code "52") (name "/IN_FX2") (class "Default")
      (node (ref "R19") (pin "1") (pinfunction "1_1") (pintype "passive"))
      (node (ref "U$2") (pin "16") (pinfunction "16_16") (pintype "passive"))
    )
    (net (code "53") (name "/IN_O1") (class "Default")
      (node (ref "DA1") (pin "15") (pinfunction "IN4_15") (pintype "input"))
      (node (ref "R37") (pin "2") (pinfunction "2_2") (pintype "passive"))
    )
    (net (code "54") (name "/IN_O2") (class "Default")
      (node (ref "DA1") (pin "2") (pinfunction "IN1_2") (pintype "input"))
      (node (ref "R28") (pin "2") (pinfunction "2_2") (pintype "passive"))
    )
    (net (code "55") (name "/IN_O3") (class "Default")
      (node (ref "DA1") (pin "10") (pinfunction "IN3_10") (pintype "input"))
      (node (ref "R34") (pin "2") (pinfunction "2_2") (pintype "passive"))
    )
    (net (code "56") (name "/IN_O4") (class "Default")
      (node (ref "DA1") (pin "7") (pinfunction "IN2_7") (pintype "input"))
      (node (ref "R31") (pin "2") (pinfunction "2_2") (pintype "passive"))
    )
    (net (code "57") (name "/N$19") (class "Default")
      (node (ref "DA3") (pin "12") (pinfunction "OUT3_12") (pintype "output"))
      (node (ref "IC6") (pin "5") (pinfunction "+IN_5") (pintype "input"))
      (node (ref "R47") (pin "1") (pinfunction "1_1") (pintype "passive"))
    )
    (net (code "58") (name "/OUT1") (class "Default")
      (node (ref "IC3") (pin "7") (pinfunction "OUT_7") (pintype "output"))
      (node (ref "R44") (pin "1") (pinfunction "1_1") (pintype "passive"))
      (node (ref "R59") (pin "1") (pinfunction "1_1") (pintype "passive"))
      (node (ref "R60") (pin "1") (pinfunction "1_1") (pintype "passive"))
    )
    (net (code "59") (name "/OUT2") (class "Default")
      (node (ref "IC3") (pin "1") (pinfunction "OUT_1") (pintype "output"))
      (node (ref "R41") (pin "1") (pinfunction "1_1") (pintype "passive"))
      (node (ref "R53") (pin "1") (pinfunction "1_1") (pintype "passive"))
      (node (ref "R54") (pin "1") (pinfunction "1_1") (pintype "passive"))
    )
    (net (code "60") (name "/OUT3") (class "Default")
      (node (ref "IC5") (pin "7") (pinfunction "OUT_7") (pintype "output"))
      (node (ref "R43") (pin "1") (pinfunction "1_1") (pintype "passive"))
      (node (ref "R57") (pin "1") (pinfunction "1_1") (pintype "passive"))
      (node (ref "R58") (pin "1") (pinfunction "1_1") (pintype "passive"))
    )
    (net (code "61") (name "/OUT4") (class "Default")
      (node (ref "IC5") (pin "1") (pinfunction "OUT_1") (pintype "output"))
      (node (ref "R42") (pin "1") (pinfunction "1_1") (pintype "passive"))
      (node (ref "R55") (pin "1") (pinfunction "1_1") (pintype "passive"))
      (node (ref "R56") (pin "1") (pinfunction "1_1") (pintype "passive"))
    )
    (net (code "62") (name "/OUT5") (class "Default")
      (node (ref "IC2") (pin "1") (pinfunction "OUT_1") (pintype "output"))
      (node (ref "R48") (pin "1") (pinfunction "1_1") (pintype "passive"))
      (node (ref "R67") (pin "1") (pinfunction "1_1") (pintype "passive"))
      (node (ref "R68") (pin "1") (pinfunction "1_1") (pintype "passive"))
    )
    (net (code "63") (name "/OUT6") (class "Default")
      (node (ref "IC2") (pin "14") (pinfunction "OUT_14") (pintype "output"))
      (node (ref "R45") (pin "1") (pinfunction "1_1") (pintype "passive"))
      (node (ref "R61") (pin "1") (pinfunction "1_1") (pintype "passive"))
      (node (ref "R62") (pin "1") (pinfunction "1_1") (pintype "passive"))
    )
    (net (code "64") (name "/OUT7") (class "Default")
      (node (ref "IC6") (pin "6") (pinfunction "-IN_6") (pintype "input"))
      (node (ref "IC6") (pin "7") (pinfunction "OUT_7") (pintype "output"))
      (node (ref "R65") (pin "1") (pinfunction "1_1") (pintype "passive"))
      (node (ref "R66") (pin "1") (pinfunction "1_1") (pintype "passive"))
    )
    (net (code "65") (name "/OUT8") (class "Default")
      (node (ref "IC6") (pin "1") (pinfunction "OUT_1") (pintype "output"))
      (node (ref "IC6") (pin "2") (pinfunction "-IN_2") (pintype "input"))
      (node (ref "R63") (pin "1") (pinfunction "1_1") (pintype "passive"))
      (node (ref "R64") (pin "1") (pinfunction "1_1") (pintype "passive"))
    )
    (net (code "66") (name "/OUT_A") (class "Default")
      (node (ref "IC2") (pin "7") (pinfunction "OUT_7") (pintype "output"))
      (node (ref "R52") (pin "1") (pinfunction "1_1") (pintype "passive"))
      (node (ref "U$2") (pin "2") (pinfunction "2_2") (pintype "passive"))
    )
    (net (code "67") (name "/OUT_B") (class "Default")
      (node (ref "IC2") (pin "8") (pinfunction "OUT_8") (pintype "output"))
      (node (ref "R50") (pin "1") (pinfunction "1_1") (pintype "passive"))
      (node (ref "U$2") (pin "3") (pinfunction "3_3") (pintype "passive"))
    )
    (net (code "68") (name "/SCL") (class "Default")
      (node (ref "IC1") (pin "22") (pinfunction "SCL_22") (pintype "bidirectional"))
      (node (ref "U$3") (pin "3") (pinfunction "3_3") (pintype "passive"))
    )
    (net (code "69") (name "/SDA") (class "Default")
      (node (ref "IC1") (pin "23") (pinfunction "SDA_23") (pintype "bidirectional"))
      (node (ref "U$3") (pin "2") (pinfunction "2_2") (pintype "passive"))
    )
    (net (code "70") (name "/SUM1") (class "Default")
      (node (ref "DA2") (pin "15") (pinfunction "IN4_15") (pintype "input"))
      (node (ref "R13") (pin "2") (pinfunction "2_2") (pintype "passive"))
    )
    (net (code "71") (name "/SUM2") (class "Default")
      (node (ref "DA2") (pin "2") (pinfunction "IN1_2") (pintype "input"))
      (node (ref "R4") (pin "2") (pinfunction "2_2") (pintype "passive"))
    )
    (net (code "72") (name "/SUM3") (class "Default")
      (node (ref "DA2") (pin "10") (pinfunction "IN3_10") (pintype "input"))
      (node (ref "R10") (pin "2") (pinfunction "2_2") (pintype "passive"))
    )
    (net (code "73") (name "/SUM4") (class "Default")
      (node (ref "DA2") (pin "7") (pinfunction "IN2_7") (pintype "input"))
      (node (ref "R7") (pin "2") (pinfunction "2_2") (pintype "passive"))
    )
    (net (code "74") (name "/SUM5") (class "Default")
      (node (ref "DA3") (pin "15") (pinfunction "IN4_15") (pintype "input"))
      (node (ref "R25") (pin "2") (pinfunction "2_2") (pintype "passive"))
    )
    (net (code "75") (name "/SUM6") (class "Default")
      (node (ref "DA3") (pin "2") (pinfunction "IN1_2") (pintype "input"))
      (node (ref "R16") (pin "2") (pinfunction "2_2") (pintype "passive"))
      (node (ref "R70") (pin "2") (pinfunction "2_2") (pintype "passive"))
    )
    (net (code "76") (name "/SUM7") (class "Default")
      (node (ref "DA3") (pin "10") (pinfunction "IN3_10") (pintype "input"))
      (node (ref "R22") (pin "2") (pinfunction "2_2") (pintype "passive"))
    )
    (net (code "77") (name "/SUM8") (class "Default")
      (node (ref "DA3") (pin "7") (pinfunction "IN2_7") (pintype "input"))
      (node (ref "R19") (pin "2") (pinfunction "2_2") (pintype "passive"))
    )
    (net (code "78") (name "/SUM_A") (class "Default")
      (node (ref "C24") (pin "2") (pinfunction "2_2") (pintype "passive"))
      (node (ref "IC4") (pin "1") (pinfunction "OUT_1") (pintype "output"))
      (node (ref "R37") (pin "1") (pinfunction "1_1") (pintype "passive"))
      (node (ref "R79") (pin "2") (pinfunction "2_2") (pintype "passive"))
      (node (ref "U$3") (pin "13") (pinfunction "13_13") (pintype "passive"))
    )
    (net (code "79") (name "/SUM_B") (class "Default")
      (node (ref "C25") (pin "2") (pinfunction "2_2") (pintype "passive"))
      (node (ref "IC4") (pin "14") (pinfunction "OUT_14") (pintype "output"))
      (node (ref "R28") (pin "1") (pinfunction "1_1") (pintype "passive"))
      (node (ref "R80") (pin "2") (pinfunction "2_2") (pintype "passive"))
      (node (ref "U$3") (pin "14") (pinfunction "14_14") (pintype "passive"))
    )
    (net (code "80") (name "/SUM_FX_A") (class "Default")
      (node (ref "C26") (pin "2") (pinfunction "2_2") (pintype "passive"))
      (node (ref "IC4") (pin "7") (pinfunction "OUT_7") (pintype "output"))
      (node (ref "R34") (pin "1") (pinfunction "1_1") (pintype "passive"))
      (node (ref "R81") (pin "2") (pinfunction "2_2") (pintype "passive"))
    )
    (net (code "81") (name "/SUM_FX_B") (class "Default")
      (node (ref "C27") (pin "2") (pinfunction "2_2") (pintype "passive"))
      (node (ref "IC4") (pin "8") (pinfunction "OUT_8") (pintype "output"))
      (node (ref "R31") (pin "1") (pinfunction "1_1") (pintype "passive"))
      (node (ref "R82") (pin "2") (pinfunction "2_2") (pintype "passive"))
    )
    (net (code "82") (name "/SVF_CHAIN") (class "Default")
      (node (ref "R69") (pin "2") (pinfunction "2_2") (pintype "passive"))
      (node (ref "U$3") (pin "16") (pinfunction "16_16") (pintype "passive"))
    )
    (net (code "83") (name "/SW1A") (class "Default")
      (node (ref "IC8") (pin "2") (pinfunction "D_2") (pintype "bidirectional"))
      (node (ref "R59") (pin "2") (pinfunction "2_2") (pintype "passive"))
    )
    (net (code "84") (name "/SW1B") (class "Default")
      (node (ref "IC8") (pin "15") (pinfunction "D_15") (pintype "bidirectional"))
      (node (ref "R60") (pin "2") (pinfunction "2_2") (pintype "passive"))
    )
    (net (code "85") (name "/SW2A") (class "Default")
      (node (ref "IC8") (pin "7") (pinfunction "D_7") (pintype "bidirectional"))
      (node (ref "R53") (pin "2") (pinfunction "2_2") (pintype "passive"))
    )
    (net (code "86") (name "/SW2B") (class "Default")
      (node (ref "IC8") (pin "10") (pinfunction "D_10") (pintype "bidirectional"))
      (node (ref "R54") (pin "2") (pinfunction "2_2") (pintype "passive"))
    )
    (net (code "87") (name "/SW3A") (class "Default")
      (node (ref "IC9") (pin "2") (pinfunction "D_2") (pintype "bidirectional"))
      (node (ref "R57") (pin "2") (pinfunction "2_2") (pintype "passive"))
    )
    (net (code "88") (name "/SW3B") (class "Default")
      (node (ref "IC9") (pin "15") (pinfunction "D_15") (pintype "bidirectional"))
      (node (ref "R58") (pin "2") (pinfunction "2_2") (pintype "passive"))
    )
    (net (code "89") (name "/SW4A") (class "Default")
      (node (ref "IC9") (pin "7") (pinfunction "D_7") (pintype "bidirectional"))
      (node (ref "R55") (pin "2") (pinfunction "2_2") (pintype "passive"))
    )
    (net (code "90") (name "/SW4B") (class "Default")
      (node (ref "IC9") (pin "10") (pinfunction "D_10") (pintype "bidirectional"))
      (node (ref "R56") (pin "2") (pinfunction "2_2") (pintype "passive"))
    )
    (net (code "91") (name "/SW5A") (class "Default")
      (node (ref "IC10") (pin "2") (pinfunction "D_2") (pintype "bidirectional"))
      (node (ref "R67") (pin "2") (pinfunction "2_2") (pintype "passive"))
    )
    (net (code "92") (name "/SW5B") (class "Default")
      (node (ref "IC10") (pin "15") (pinfunction "D_15") (pintype "bidirectional"))
      (node (ref "R68") (pin "2") (pinfunction "2_2") (pintype "passive"))
    )
    (net (code "93") (name "/SW6A") (class "Default")
      (node (ref "IC10") (pin "7") (pinfunction "D_7") (pintype "bidirectional"))
      (node (ref "R61") (pin "2") (pinfunction "2_2") (pintype "passive"))
    )
    (net (code "94") (name "/SW6B") (class "Default")
      (node (ref "IC10") (pin "10") (pinfunction "D_10") (pintype "bidirectional"))
      (node (ref "R62") (pin "2") (pinfunction "2_2") (pintype "passive"))
    )
    (net (code "95") (name "/SW7A") (class "Default")
      (node (ref "IC11") (pin "2") (pinfunction "D_2") (pintype "bidirectional"))
      (node (ref "R65") (pin "2") (pinfunction "2_2") (pintype "passive"))
    )
    (net (code "96") (name "/SW7B") (class "Default")
      (node (ref "IC11") (pin "15") (pinfunction "D_15") (pintype "bidirectional"))
      (node (ref "R66") (pin "2") (pinfunction "2_2") (pintype "passive"))
    )
    (net (code "97") (name "/SW8A") (class "Default")
      (node (ref "IC11") (pin "7") (pinfunction "D_7") (pintype "bidirectional"))
      (node (ref "R63") (pin "2") (pinfunction "2_2") (pintype "passive"))
    )
    (net (code "98") (name "/SW8B") (class "Default")
      (node (ref "IC11") (pin "10") (pinfunction "D_10") (pintype "bidirectional"))
      (node (ref "R64") (pin "2") (pinfunction "2_2") (pintype "passive"))
    )
    (net (code "99") (name "/VL") (class "Default")
      (node (ref "IC10") (pin "12") (pinfunction "VL_12") (pintype "bidirectional"))
      (node (ref "IC11") (pin "12") (pinfunction "VL_12") (pintype "bidirectional"))
      (node (ref "IC8") (pin "12") (pinfunction "VL_12") (pintype "bidirectional"))
      (node (ref "IC9") (pin "12") (pinfunction "VL_12") (pintype "bidirectional"))
      (node (ref "R77") (pin "2") (pinfunction "2_2") (pintype "passive"))
      (node (ref "R78") (pin "1") (pinfunction "1_1") (pintype "passive"))
    )
    (net (code "100") (name "/~{RST}") (class "Default")
      (node (ref "IC1") (pin "3") (pinfunction "~{RESET}_3") (pintype "bidirectional"))
      (node (ref "R1") (pin "2") (pinfunction "2_2") (pintype "passive"))
    )
    (net (code "101") (name "DGND") (class "Default")
      (node (ref "C23") (pin "1") (pinfunction "1_1") (pintype "passive"))
      (node (ref "IC1") (pin "12") (pinfunction "VSS_12") (pintype "power_in"))
      (node (ref "IC1") (pin "2") (pinfunction "A1_2") (pintype "bidirectional"))
      (node (ref "IC1") (pin "21") (pinfunction "A0_21") (pintype "bidirectional"))
      (node (ref "U$3") (pin "4") (pinfunction "4_4") (pintype "passive"))
    )
    (net (code "102") (name "GND") (class "Default")
      (node (ref "C1") (pin "1") (pinfunction "1_1") (pintype "passive"))
      (node (ref "C10") (pin "2") (pinfunction "2_2") (pintype "passive"))
      (node (ref "C11") (pin "1") (pinfunction "1_1") (pintype "passive"))
      (node (ref "C12") (pin "2") (pinfunction "2_2") (pintype "passive"))
      (node (ref "C13") (pin "1") (pinfunction "1_1") (pintype "passive"))
      (node (ref "C14") (pin "1") (pinfunction "1_1") (pintype "passive"))
      (node (ref "C15") (pin "1") (pinfunction "1_1") (pintype "passive"))
      (node (ref "C16") (pin "1") (pinfunction "1_1") (pintype "passive"))
      (node (ref "C17") (pin "2") (pinfunction "2_2") (pintype "passive"))
      (node (ref "C2") (pin "2") (pinfunction "2_2") (pintype "passive"))
      (node (ref "C3") (pin "1") (pinfunction "1_1") (pintype "passive"))
      (node (ref "C4") (pin "2") (pinfunction "2_2") (pintype "passive"))
      (node (ref "C5") (pin "1") (pinfunction "1_1") (pintype "passive"))
      (node (ref "C6") (pin "2") (pinfunction "2_2") (pintype "passive"))
      (node (ref "C7") (pin "1") (pinfunction "1_1") (pintype "passive"))
      (node (ref "C8") (pin "2") (pinfunction "2_2") (pintype "passive"))
      (node (ref "C9") (pin "1") (pinfunction "1_1") (pintype "passive"))
      (node (ref "DA1") (pin "8") (pinfunction "GND_8") (pintype "power_in"))
      (node (ref "DA2") (pin "8") (pinfunction "GND_8") (pintype "power_in"))
      (node (ref "DA3") (pin "8") (pinfunction "GND_8") (pintype "power_in"))
      (node (ref "IC10") (pin "5") (pinfunction "AGND_5") (pintype "power_in"))
      (node (ref "IC11") (pin "5") (pinfunction "AGND_5") (pintype "power_in"))
      (node (ref "IC2") (pin "12") (pinfunction "+IN_12") (pintype "input"))
      (node (ref "IC2") (pin "3") (pinfunction "+IN_3") (pintype "input"))
      (node (ref "IC3") (pin "3") (pinfunction "+IN_3") (pintype "input"))
      (node (ref "IC3") (pin "5") (pinfunction "+IN_5") (pintype "input"))
      (node (ref "IC4") (pin "10") (pinfunction "+IN_10") (pintype "input"))
      (node (ref "IC4") (pin "12") (pinfunction "+IN_12") (pintype "input"))
      (node (ref "IC4") (pin "3") (pinfunction "+IN_3") (pintype "input"))
      (node (ref "IC4") (pin "5") (pinfunction "+IN_5") (pintype "input"))
      (node (ref "IC5") (pin "3") (pinfunction "+IN_3") (pintype "input"))
      (node (ref "IC5") (pin "5") (pinfunction "+IN_5") (pintype "input"))
      (node (ref "IC8") (pin "5") (pinfunction "AGND_5") (pintype "power_in"))
      (node (ref "IC9") (pin "5") (pinfunction "AGND_5") (pintype "power_in"))
      (node (ref "R12") (pin "1") (pinfunction "1_1") (pintype "passive"))
      (node (ref "R15") (pin "1") (pinfunction "1_1") (pintype "passive"))
      (node (ref "R18") (pin "1") (pinfunction "1_1") (pintype "passive"))
      (node (ref "R21") (pin "1") (pinfunction "1_1") (pintype "passive"))
      (node (ref "R24") (pin "1") (pinfunction "1_1") (pintype "passive"))
      (node (ref "R27") (pin "1") (pinfunction "1_1") (pintype "passive"))
      (node (ref "R3") (pin "1") (pinfunction "1_1") (pintype "passive"))
      (node (ref "R30") (pin "1") (pinfunction "1_1") (pintype "passive"))
      (node (ref "R33") (pin "1") (pinfunction "1_1") (pintype "passive"))
      (node (ref "R36") (pin "1") (pinfunction "1_1") (pintype "passive"))
      (node (ref "R46") (pin "2") (pinfunction "2_2") (pintype "passive"))
      (node (ref "R47") (pin "2") (pinfunction "2_2") (pintype "passive"))
      (node (ref "R49") (pin "2") (pinfunction "2_2") (pintype "passive"))
      (node (ref "R51") (pin "2") (pinfunction "2_2") (pintype "passive"))
      (node (ref "R6") (pin "1") (pinfunction "1_1") (pintype "passive"))
      (node (ref "R73") (pin "1") (pinfunction "1_1") (pintype "passive"))
      (node (ref "R74") (pin "1") (pinfunction "1_1") (pintype "passive"))
      (node (ref "R75") (pin "1") (pinfunction "1_1") (pintype "passive"))
      (node (ref "R76") (pin "1") (pinfunction "1_1") (pintype "passive"))
      (node (ref "R78") (pin "2") (pinfunction "2_2") (pintype "passive"))
      (node (ref "R9") (pin "1") (pinfunction "1_1") (pintype "passive"))
      (node (ref "U$2") (pin "7") (pinfunction "7_7") (pintype "passive"))
    )
    (net (code "103") (name "Net-(C13-Pad2)") (class "Default")
      (node (ref "C13") (pin "2") (pinfunction "2_2") (pintype "passive"))
      (node (ref "R38") (pin "1") (pinfunction "1_1") (pintype "passive"))
    )
    (net (code "104") (name "Net-(C14-Pad2)") (class "Default")
      (node (ref "C14") (pin "2") (pinfunction "2_2") (pintype "passive"))
      (node (ref "R39") (pin "1") (pinfunction "1_1") (pintype "passive"))
    )
    (net (code "105") (name "Net-(C15-Pad2)") (class "Default")
      (node (ref "C15") (pin "2") (pinfunction "2_2") (pintype "passive"))
      (node (ref "R40") (pin "1") (pinfunction "1_1") (pintype "passive"))
    )
    (net (code "106") (name "Net-(DA1B-CV2)") (class "Default")
      (node (ref "DA1") (pin "6") (pinfunction "CV2_6") (pintype "input"))
      (node (ref "R29") (pin "2") (pinfunction "2_2") (pintype "passive"))
      (node (ref "R30") (pin "2") (pinfunction "2_2") (pintype "passive"))
    )
    (net (code "107") (name "Net-(DA1B-CV3)") (class "Default")
      (node (ref "DA1") (pin "11") (pinfunction "CV3_11") (pintype "input"))
      (node (ref "R32") (pin "2") (pinfunction "2_2") (pintype "passive"))
      (node (ref "R33") (pin "2") (pinfunction "2_2") (pintype "passive"))
    )
    (net (code "108") (name "Net-(DA1B-CV4)") (class "Default")
      (node (ref "DA1") (pin "14") (pinfunction "CV4_14") (pintype "input"))
      (node (ref "R35") (pin "2") (pinfunction "2_2") (pintype "passive"))
      (node (ref "R36") (pin "2") (pinfunction "2_2") (pintype "passive"))
    )
    (net (code "109") (name "Net-(DA1B-OUT1)") (class "Default")
      (node (ref "DA1") (pin "4") (pinfunction "OUT1_4") (pintype "output"))
      (node (ref "IC2") (pin "10") (pinfunction "+IN_10") (pintype "input"))
      (node (ref "R51") (pin "1") (pinfunction "1_1") (pintype "passive"))
    )
    (net (code "110") (name "Net-(DA1B-OUT2)") (class "Default")
      (node (ref "DA1") (pin "5") (pinfunction "OUT2_5") (pintype "output"))
      (node (ref "IC2") (pin "9") (pinfunction "-IN_9") (pintype "input"))
      (node (ref "R50") (pin "2") (pinfunction "2_2") (pintype "passive"))
      (node (ref "R69") (pin "1") (pinfunction "1_1") (pintype "passive"))
    )
    (net (code "111") (name "Net-(DA1B-OUT3)") (class "Default")
      (node (ref "DA1") (pin "12") (pinfunction "OUT3_12") (pintype "output"))
      (node (ref "IC2") (pin "6") (pinfunction "-IN_6") (pintype "input"))
      (node (ref "R52") (pin "2") (pinfunction "2_2") (pintype "passive"))
    )
    (net (code "112") (name "Net-(DA1B-OUT4)") (class "Default")
      (node (ref "DA1") (pin "13") (pinfunction "OUT4_13") (pintype "output"))
      (node (ref "IC2") (pin "5") (pinfunction "+IN_5") (pintype "input"))
      (node (ref "R49") (pin "1") (pinfunction "1_1") (pintype "passive"))
    )
    (net (code "113") (name "Net-(DA1B-VREF)") (class "Default")
      (node (ref "DA1") (pin "1") (pinfunction "VREF_1") (pintype "output"))
      (node (ref "R40") (pin "2") (pinfunction "2_2") (pintype "passive"))
    )
    (net (code "114") (name "Net-(DA2B-CV2)") (class "Default")
      (node (ref "DA2") (pin "6") (pinfunction "CV2_6") (pintype "input"))
      (node (ref "R5") (pin "2") (pinfunction "2_2") (pintype "passive"))
      (node (ref "R6") (pin "2") (pinfunction "2_2") (pintype "passive"))
    )
    (net (code "115") (name "Net-(DA2B-CV3)") (class "Default")
      (node (ref "DA2") (pin "11") (pinfunction "CV3_11") (pintype "input"))
      (node (ref "R8") (pin "2") (pinfunction "2_2") (pintype "passive"))
      (node (ref "R9") (pin "2") (pinfunction "2_2") (pintype "passive"))
    )
    (net (code "116") (name "Net-(DA2B-CV4)") (class "Default")
      (node (ref "DA2") (pin "14") (pinfunction "CV4_14") (pintype "input"))
      (node (ref "R11") (pin "2") (pinfunction "2_2") (pintype "passive"))
      (node (ref "R12") (pin "2") (pinfunction "2_2") (pintype "passive"))
    )
    (net (code "117") (name "Net-(DA2B-VREF)") (class "Default")
      (node (ref "DA2") (pin "1") (pinfunction "VREF_1") (pintype "output"))
      (node (ref "R38") (pin "2") (pinfunction "2_2") (pintype "passive"))
    )
    (net (code "118") (name "Net-(DA3B-CV2)") (class "Default")
      (node (ref "DA3") (pin "6") (pinfunction "CV2_6") (pintype "input"))
      (node (ref "R17") (pin "2") (pinfunction "2_2") (pintype "passive"))
      (node (ref "R18") (pin "2") (pinfunction "2_2") (pintype "passive"))
    )
    (net (code "119") (name "Net-(DA3B-CV3)") (class "Default")
      (node (ref "DA3") (pin "11") (pinfunction "CV3_11") (pintype "input"))
      (node (ref "R20") (pin "2") (pinfunction "2_2") (pintype "passive"))
      (node (ref "R21") (pin "2") (pinfunction "2_2") (pintype "passive"))
    )
    (net (code "120") (name "Net-(DA3B-CV4)") (class "Default")
      (node (ref "DA3") (pin "14") (pinfunction "CV4_14") (pintype "input"))
      (node (ref "R23") (pin "2") (pinfunction "2_2") (pintype "passive"))
      (node (ref "R24") (pin "2") (pinfunction "2_2") (pintype "passive"))
    )
    (net (code "121") (name "Net-(DA3B-OUT2)") (class "Default")
      (node (ref "DA3") (pin "5") (pinfunction "OUT2_5") (pintype "output"))
      (node (ref "IC6") (pin "3") (pinfunction "+IN_3") (pintype "input"))
      (node (ref "R46") (pin "1") (pinfunction "1_1") (pintype "passive"))
    )
    (net (code "122") (name "Net-(DA3B-VREF)") (class "Default")
      (node (ref "DA3") (pin "1") (pinfunction "VREF_1") (pintype "output"))
      (node (ref "R39") (pin "2") (pinfunction "2_2") (pintype "passive"))
    )
    (net (code "123") (name "unconnected-(IC1-~{INT}-Pad1)") (class "Default")
      (node (ref "IC1") (pin "1") (pinfunction "~{INT}_1") (pintype "bidirectional"))
    )
  )
)
